# temprature_control.net
KiCad netlist of a schematic drawn in EAGLE
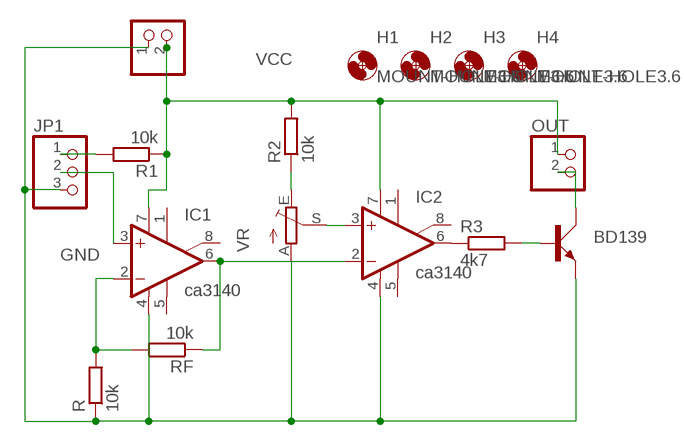
[diagram p0: schematic, sheet 1]

(export (version "E")
  (design (tool "Eeschema 10.0.6"))
  (components
    (comp (ref "H1")
      (value "MOUNT-HOLE3.6")
      (footprint "eagle-import:3,6")
      (libsource (lib "eagle-import") (part "MOUNT-HOLE3.6"))
    )
    (comp (ref "H2")
      (value "MOUNT-HOLE3.6")
      (footprint "eagle-import:3,6")
      (libsource (lib "eagle-import") (part "MOUNT-HOLE3.6"))
    )
    (comp (ref "H3")
      (value "MOUNT-HOLE3.6")
      (footprint "eagle-import:3,6")
      (libsource (lib "eagle-import") (part "MOUNT-HOLE3.6"))
    )
    (comp (ref "H4")
      (value "MOUNT-HOLE3.6")
      (footprint "eagle-import:3,6")
      (libsource (lib "eagle-import") (part "MOUNT-HOLE3.6"))
    )
    (comp (ref "IC1")
      (value "ca3140")
      (footprint "eagle-import:DIL08")
      (libsource (lib "eagle-import") (part "3080NLM"))
    )
    (comp (ref "IC2")
      (value "ca3140")
      (footprint "eagle-import:DIL08")
      (libsource (lib "eagle-import") (part "3080NLM"))
    )
    (comp (ref "JP1")
      (value "PINHD-1X3")
      (footprint "eagle-import:1X03")
      (libsource (lib "eagle-import") (part "PINHD-1X3"))
    )
    (comp (ref "OUT")
      (value "PINHD-1X2")
      (footprint "eagle-import:1X02")
      (libsource (lib "eagle-import") (part "PINHD-1X2"))
    )
    (comp (ref "Q1")
      (value "BD139")
      (footprint "eagle-import:TO126AV")
      (libsource (lib "eagle-import") (part "BD139"))
    )
    (comp (ref "R")
      (value "10k")
      (footprint "eagle-import:0207_15")
      (libsource (lib "eagle-import") (part "R-EU_0207/15"))
    )
    (comp (ref "R1")
      (value "10k")
      (footprint "eagle-import:0207_15")
      (libsource (lib "eagle-import") (part "R-EU_0207/15"))
    )
    (comp (ref "R2")
      (value "10k")
      (footprint "eagle-import:0207_15")
      (libsource (lib "eagle-import") (part "R-EU_0207/15"))
    )
    (comp (ref "R3")
      (value "4k7")
      (footprint "eagle-import:0207_15")
      (libsource (lib "eagle-import") (part "R-EU_0207/15"))
    )
    (comp (ref "RF")
      (value "10k")
      (footprint "eagle-import:0207_15")
      (libsource (lib "eagle-import") (part "R-EU_0207/15"))
    )
    (comp (ref "VCC")
      (value "PINHD-1X2")
      (footprint "eagle-import:1X02")
      (libsource (lib "eagle-import") (part "PINHD-1X2"))
    )
    (comp (ref "VR")
      (value "TRIM_EU-LI10")
      (footprint "eagle-import:LI10")
      (libsource (lib "eagle-import") (part "TRIM_EU-LI10"))
    )
  )
  (nets
    (net (code "1") (name "/GND") (class "Default")
      (node (ref "IC1") (pin "4") (pinfunction "V-_4") (pintype "power_in"))
      (node (ref "IC2") (pin "4") (pinfunction "V-_4") (pintype "power_in"))
      (node (ref "JP1") (pin "3") (pinfunction "3_3") (pintype "passive"))
      (node (ref "Q1") (pin "E") (pinfunction "E_E") (pintype "passive"))
      (node (ref "R") (pin "1") (pinfunction "1_1") (pintype "passive"))
      (node (ref "VCC") (pin "1") (pinfunction "1_1") (pintype "passive"))
      (node (ref "VR") (pin "A") (pinfunction "A_A") (pintype "passive"))
    )
    (net (code "2") (name "/VCC") (class "Default")
      (node (ref "IC1") (pin "7") (pinfunction "V+_7") (pintype "power_in"))
      (node (ref "IC2") (pin "7") (pinfunction "V+_7") (pintype "power_in"))
      (node (ref "OUT") (pin "1") (pinfunction "1_1") (pintype "passive"))
      (node (ref "R1") (pin "1") (pinfunction "1_1") (pintype "passive"))
      (node (ref "R2") (pin "2") (pinfunction "2_2") (pintype "passive"))
      (node (ref "VCC") (pin "2") (pinfunction "2_2") (pintype "passive"))
    )
    (net (code "3") (name "Net-(IC1-+IN)") (class "Default")
      (node (ref "IC1") (pin "3") (pinfunction "+IN_3") (pintype "input"))
      (node (ref "JP1") (pin "2") (pinfunction "2_2") (pintype "passive"))
    )
    (net (code "4") (name "Net-(IC1--IN)") (class "Default")
      (node (ref "IC1") (pin "2") (pinfunction "-IN_2") (pintype "input"))
      (node (ref "R") (pin "2") (pinfunction "2_2") (pintype "passive"))
      (node (ref "RF") (pin "2") (pinfunction "2_2") (pintype "passive"))
    )
    (net (code "5") (name "Net-(IC1-OUT)") (class "Default")
      (node (ref "IC1") (pin "6") (pinfunction "OUT_6") (pintype "output"))
      (node (ref "IC2") (pin "2") (pinfunction "-IN_2") (pintype "input"))
      (node (ref "RF") (pin "1") (pinfunction "1_1") (pintype "passive"))
    )
    (net (code "6") (name "Net-(IC2-+IN)") (class "Default")
      (node (ref "IC2") (pin "3") (pinfunction "+IN_3") (pintype "input"))
      (node (ref "VR") (pin "S") (pinfunction "S_S") (pintype "passive"))
    )
    (net (code "7") (name "Net-(IC2-OUT)") (class "Default")
      (node (ref "IC2") (pin "6") (pinfunction "OUT_6") (pintype "output"))
      (node (ref "R3") (pin "1") (pinfunction "1_1") (pintype "passive"))
    )
    (net (code "8") (name "Net-(JP1-Pad1)") (class "Default")
      (node (ref "JP1") (pin "1") (pinfunction "1_1") (pintype "passive"))
      (node (ref "R1") (pin "2") (pinfunction "2_2") (pintype "passive"))
    )
    (net (code "9") (name "Net-(OUT-Pad2)") (class "Default")
      (node (ref "OUT") (pin "2") (pinfunction "2_2") (pintype "passive"))
      (node (ref "Q1") (pin "C") (pinfunction "C_C") (pintype "passive"))
    )
    (net (code "10") (name "Net-(Q1-PadB)") (class "Default")
      (node (ref "Q1") (pin "B") (pinfunction "B_B") (pintype "passive"))
      (node (ref "R3") (pin "2") (pinfunction "2_2") (pintype "passive"))
    )
    (net (code "11") (name "Net-(R2-Pad1)") (class "Default")
      (node (ref "R2") (pin "1") (pinfunction "1_1") (pintype "passive"))
      (node (ref "VR") (pin "E") (pinfunction "E_E") (pintype "passive"))
    )
    (net (code "12") (name "unconnected-(IC1-ON1-Pad1)") (class "Default")
      (node (ref "IC1") (pin "1") (pinfunction "ON1_1") (pintype "passive"))
    )
    (net (code "13") (name "unconnected-(IC1-ON2-Pad8)") (class "Default")
      (node (ref "IC1") (pin "8") (pinfunction "ON2_8") (pintype "passive"))
    )
    (net (code "14") (name "unconnected-(IC1-OPT-Pad5)") (class "Default")
      (node (ref "IC1") (pin "5") (pinfunction "OPT_5") (pintype "passive"))
    )
    (net (code "15") (name "unconnected-(IC2-ON1-Pad1)") (class "Default")
      (node (ref "IC2") (pin "1") (pinfunction "ON1_1") (pintype "passive"))
    )
    (net (code "16") (name "unconnected-(IC2-ON2-Pad8)") (class "Default")
      (node (ref "IC2") (pin "8") (pinfunction "ON2_8") (pintype "passive"))
    )
    (net (code "17") (name "unconnected-(IC2-OPT-Pad5)") (class "Default")
      (node (ref "IC2") (pin "5") (pinfunction "OPT_5") (pintype "passive"))
    )
  )
)
